# Starboard_Headers.net
KiCad netlist of a schematic drawn in Altium Designer
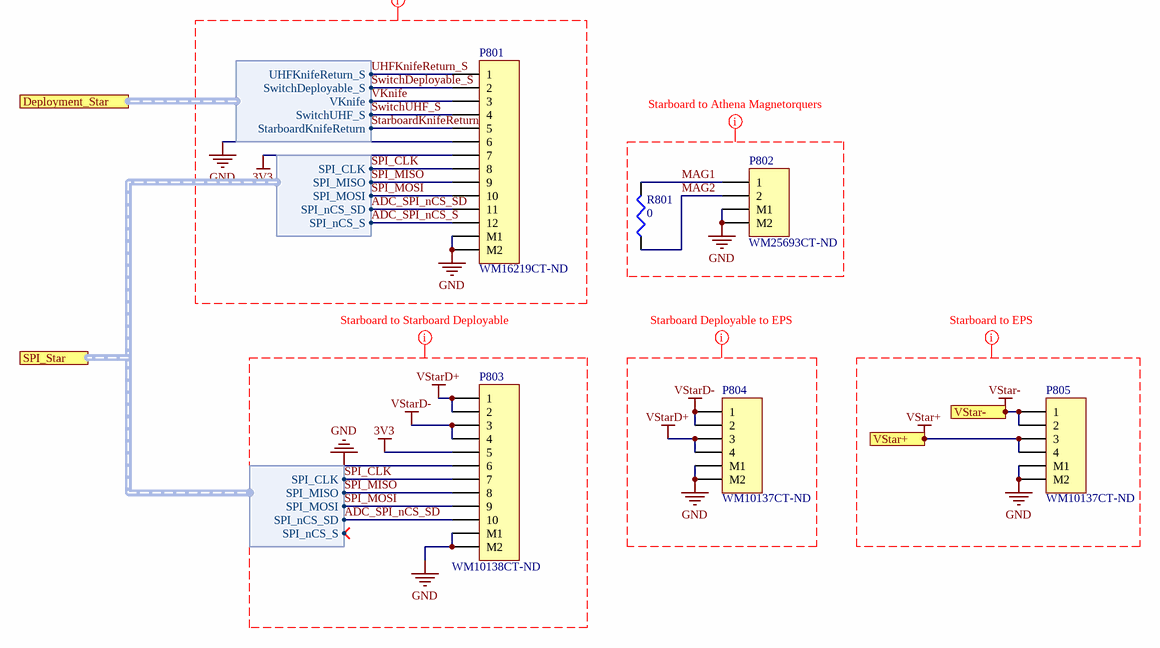
[diagram p0: Starboard_Headers.SchDoc]

(export (version "E")
  (design (tool "Eeschema 10.0.6"))
  (components
    (comp (ref "P801")
      (value "WM16219CT-ND")
      (footprint "MOLX-5040501291")
      (description "CONN HEADER SMD R/A 12POS 1.5MM")
      (fields
        (field (name "PART NUMBER") "71")
        (field (name "MANUFACTURER PART NUMBER") "5040501291")
        (field (name "PUBLISHER") "Altium Limited")
      )
      (libsource (lib "Database") (part "Header 14"))
    )
    (comp (ref "P802")
      (value "WM25693CT-ND")
      (footprint "MOLX-5040500291")
      (description "CONN HEADER SMD R/A 2POS 1.5MM")
      (fields
        (field (name "PART NUMBER") "61")
        (field (name "MANUFACTURER PART NUMBER") "5040500291")
        (field (name "PUBLISHER") "Altium Limited")
      )
      (libsource (lib "Database") (part "Header 4"))
    )
    (comp (ref "P803")
      (value "WM10138CT-ND")
      (footprint "MOLX-5040501091")
      (description "CONN HEADER SMD R/A 10POS 1.5MM")
      (fields
        (field (name "PART NUMBER") "69")
        (field (name "MANUFACTURER PART NUMBER") "5040501091")
        (field (name "PUBLISHER") "Altium Limited")
      )
      (libsource (lib "Database") (part "Header 12"))
    )
    (comp (ref "P804")
      (value "WM10137CT-ND")
      (footprint "MOLX-5040500491")
      (description "CONN HEADER SMD R/A 4POS 1.5MM")
      (fields
        (field (name "PART NUMBER") "63")
        (field (name "MANUFACTURER PART NUMBER") "5040500491")
        (field (name "PUBLISHER") "Altium Limited")
      )
      (libsource (lib "Database") (part "Header 6"))
    )
    (comp (ref "P805")
      (value "WM10137CT-ND")
      (footprint "MOLX-5040500491")
      (description "CONN HEADER SMD R/A 4POS 1.5MM")
      (fields
        (field (name "PART NUMBER") "63")
        (field (name "MANUFACTURER PART NUMBER") "5040500491")
        (field (name "PUBLISHER") "Altium Limited")
      )
      (libsource (lib "Database") (part "Header 6"))
    )
    (comp (ref "R801")
      (value "0")
      (footprint "VSH-0805MCU")
      (description "RES SMD 0.0 OHM JUMPER 1/5W 0805")
      (fields
        (field (name "PART NUMBER") "PR-VSH-00003")
        (field (name "MANUFACTURER PART NUMBER") "MCU08050Z0000ZP500")
        (field (name "PUBLISHER") "AlbertaSat")
      )
      (libsource (lib "Database") (part "Res3"))
    )
  )
  (nets
    (net (code "3") (name "/ADC_SPI_nCS_S") (class "Default")
      (node (ref "P801") (pin "12") (pinfunction "12_12") (pintype "passive"))
    )
    (net (code "4") (name "/ADC_SPI_nCS_SD") (class "Default")
      (node (ref "P801") (pin "11") (pinfunction "11_11") (pintype "passive"))
      (node (ref "P803") (pin "10") (pinfunction "10_10") (pintype "passive"))
    )
    (net (code "5") (name "/MAG1") (class "Default")
      (node (ref "P802") (pin "1") (pinfunction "1_1") (pintype "passive"))
      (node (ref "R801") (pin "2") (pinfunction "2_2") (pintype "passive"))
    )
    (net (code "6") (name "/MAG2") (class "Default")
      (node (ref "P802") (pin "2") (pinfunction "2_2") (pintype "passive"))
      (node (ref "R801") (pin "1") (pinfunction "1_1") (pintype "passive"))
    )
    (net (code "7") (name "/SPI_CLK") (class "Default")
      (node (ref "P801") (pin "8") (pinfunction "8_8") (pintype "passive"))
      (node (ref "P803") (pin "7") (pinfunction "7_7") (pintype "passive"))
    )
    (net (code "8") (name "/SPI_MISO") (class "Default")
      (node (ref "P801") (pin "9") (pinfunction "9_9") (pintype "passive"))
      (node (ref "P803") (pin "8") (pinfunction "8_8") (pintype "passive"))
    )
    (net (code "9") (name "/SPI_MOSI") (class "Default")
      (node (ref "P801") (pin "10") (pinfunction "10_10") (pintype "passive"))
      (node (ref "P803") (pin "9") (pinfunction "9_9") (pintype "passive"))
    )
    (net (code "10") (name "/StarboardKnifeReturn") (class "Default")
      (node (ref "P801") (pin "5") (pinfunction "5_5") (pintype "passive"))
    )
    (net (code "11") (name "/SwitchDeployable_S") (class "Default")
      (node (ref "P801") (pin "2") (pinfunction "2_2") (pintype "passive"))
    )
    (net (code "12") (name "/SwitchUHF_S") (class "Default")
      (node (ref "P801") (pin "4") (pinfunction "4_4") (pintype "passive"))
    )
    (net (code "13") (name "/UHFKnifeReturn_S") (class "Default")
      (node (ref "P801") (pin "1") (pinfunction "1_1") (pintype "passive"))
    )
    (net (code "14") (name "/VKnife") (class "Default")
      (node (ref "P801") (pin "3") (pinfunction "3_3") (pintype "passive"))
    )
    (net (code "17") (name "3V3") (class "Default")
      (node (ref "P801") (pin "7") (pinfunction "7_7") (pintype "passive"))
      (node (ref "P803") (pin "5") (pinfunction "5_5") (pintype "passive"))
    )
    (net (code "18") (name "GND") (class "Default")
      (node (ref "P801") (pin "6") (pinfunction "6_6") (pintype "passive"))
      (node (ref "P801") (pin "M1") (pinfunction "M1_M1") (pintype "passive"))
      (node (ref "P801") (pin "M2") (pinfunction "M2_M2") (pintype "passive"))
      (node (ref "P802") (pin "M1") (pinfunction "M1_M1") (pintype "passive"))
      (node (ref "P802") (pin "M2") (pinfunction "M2_M2") (pintype "passive"))
      (node (ref "P803") (pin "6") (pinfunction "6_6") (pintype "passive"))
      (node (ref "P803") (pin "M1") (pinfunction "M1_M1") (pintype "passive"))
      (node (ref "P803") (pin "M2") (pinfunction "M2_M2") (pintype "passive"))
      (node (ref "P804") (pin "M1") (pinfunction "M1_M1") (pintype "passive"))
      (node (ref "P804") (pin "M2") (pinfunction "M2_M2") (pintype "passive"))
      (node (ref "P805") (pin "M1") (pinfunction "M1_M1") (pintype "passive"))
      (node (ref "P805") (pin "M2") (pinfunction "M2_M2") (pintype "passive"))
    )
    (net (code "19") (name "VStar+") (class "Default")
      (node (ref "P805") (pin "3") (pinfunction "3_3") (pintype "passive"))
      (node (ref "P805") (pin "4") (pinfunction "4_4") (pintype "passive"))
    )
    (net (code "20") (name "VStar-") (class "Default")
      (node (ref "P805") (pin "1") (pinfunction "1_1") (pintype "passive"))
      (node (ref "P805") (pin "2") (pinfunction "2_2") (pintype "passive"))
    )
    (net (code "21") (name "VStarD+") (class "Default")
      (node (ref "P803") (pin "1") (pinfunction "1_1") (pintype "passive"))
      (node (ref "P803") (pin "2") (pinfunction "2_2") (pintype "passive"))
      (node (ref "P804") (pin "3") (pinfunction "3_3") (pintype "passive"))
      (node (ref "P804") (pin "4") (pinfunction "4_4") (pintype "passive"))
    )
    (net (code "22") (name "VStarD-") (class "Default")
      (node (ref "P803") (pin "3") (pinfunction "3_3") (pintype "passive"))
      (node (ref "P803") (pin "4") (pinfunction "4_4") (pintype "passive"))
      (node (ref "P804") (pin "1") (pinfunction "1_1") (pintype "passive"))
      (node (ref "P804") (pin "2") (pinfunction "2_2") (pintype "passive"))
    )
  )
)
